# vfd.net
KiCad netlist of a schematic drawn in EAGLE
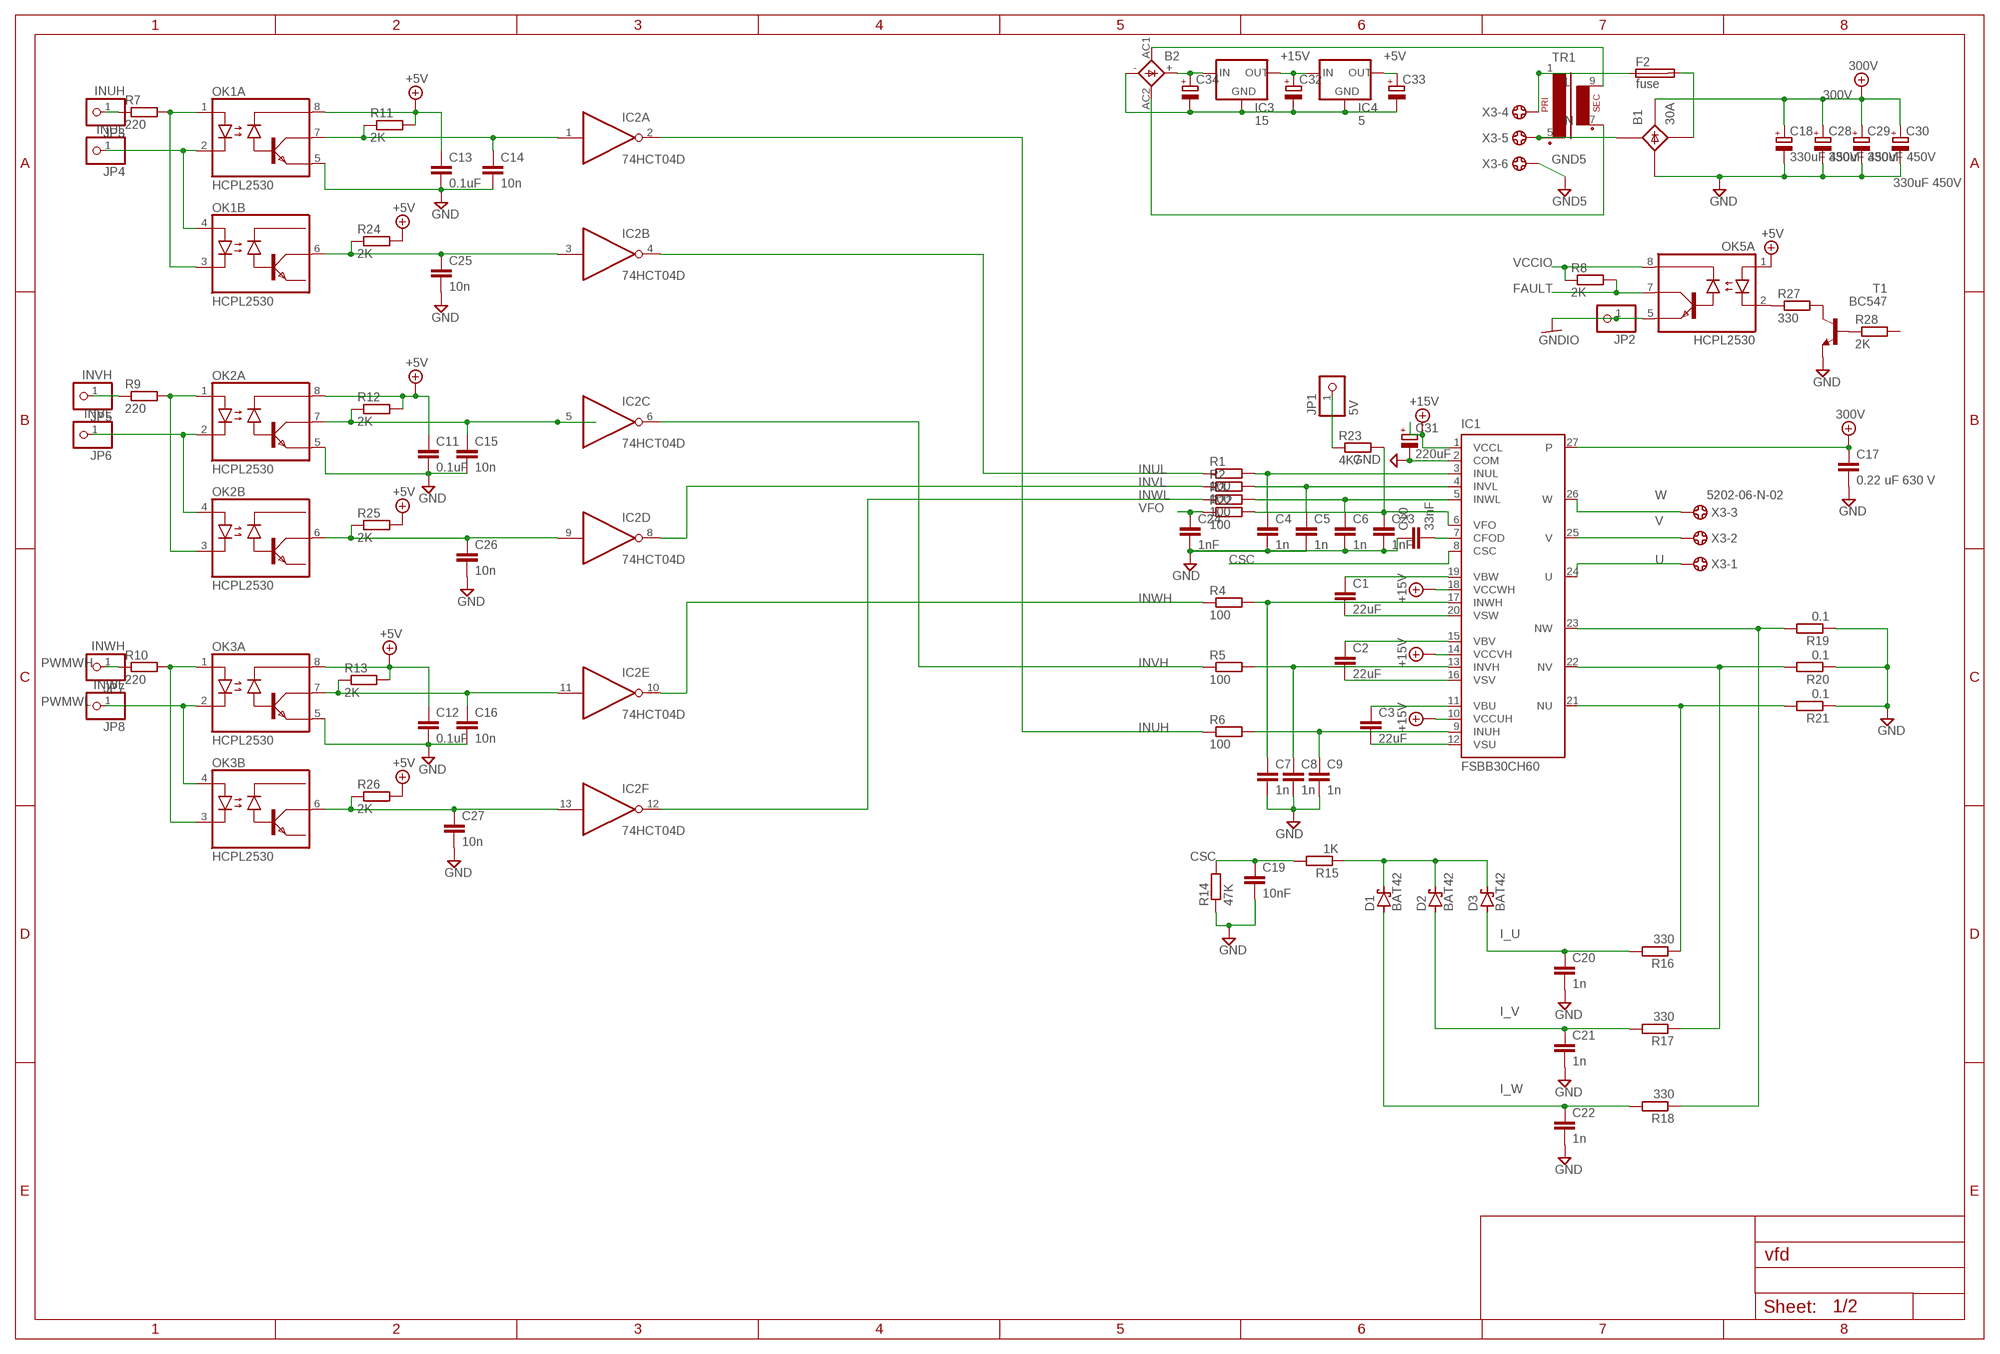
[diagram p0: schematic, sheet 1]

(export (version "E")
  (design (tool "Eeschema 10.0.6"))
  (components
    (comp (ref "B1")
      (value "30A")
      (footprint "eagle-import:B25A-")
      (libsource (lib "eagle-import") (part "B25A-"))
    )
    (comp (ref "B2")
      (value "S41")
      (footprint "eagle-import:S41")
      (libsource (lib "eagle-import") (part "S41"))
    )
    (comp (ref "C1")
      (value "22uF")
      (footprint "eagle-import:C025-024X044")
      (libsource (lib "eagle-import") (part "C-EU025-024X044"))
    )
    (comp (ref "C2")
      (value "22uF")
      (footprint "eagle-import:C025-024X044")
      (libsource (lib "eagle-import") (part "C-EU025-024X044"))
    )
    (comp (ref "C3")
      (value "22uF")
      (footprint "eagle-import:C025-024X044")
      (libsource (lib "eagle-import") (part "C-EU025-024X044"))
    )
    (comp (ref "C4")
      (value "1n")
      (footprint "eagle-import:C025-024X044")
      (libsource (lib "eagle-import") (part "C-EU025-024X044"))
    )
    (comp (ref "C5")
      (value "1n")
      (footprint "eagle-import:C025-024X044")
      (libsource (lib "eagle-import") (part "C-EU025-024X044"))
    )
    (comp (ref "C6")
      (value "1n")
      (footprint "eagle-import:C025-024X044")
      (libsource (lib "eagle-import") (part "C-EU025-024X044"))
    )
    (comp (ref "C7")
      (value "1n")
      (footprint "eagle-import:C025-024X044")
      (libsource (lib "eagle-import") (part "C-EU025-024X044"))
    )
    (comp (ref "C8")
      (value "1n")
      (footprint "eagle-import:C025-024X044")
      (libsource (lib "eagle-import") (part "C-EU025-024X044"))
    )
    (comp (ref "C9")
      (value "1n")
      (footprint "eagle-import:C025-024X044")
      (libsource (lib "eagle-import") (part "C-EU025-024X044"))
    )
    (comp (ref "C10")
      (value "33nF")
      (footprint "eagle-import:C025-024X044")
      (libsource (lib "eagle-import") (part "C-EU025-024X044"))
    )
    (comp (ref "C11")
      (value "0.1uF")
      (footprint "eagle-import:C050-025X075")
      (libsource (lib "eagle-import") (part "C-EU050-025X075"))
    )
    (comp (ref "C12")
      (value "0.1uF")
      (footprint "eagle-import:C050-025X075")
      (libsource (lib "eagle-import") (part "C-EU050-025X075"))
    )
    (comp (ref "C13")
      (value "0.1uF")
      (footprint "eagle-import:C050-025X075")
      (libsource (lib "eagle-import") (part "C-EU050-025X075"))
    )
    (comp (ref "C14")
      (value "10n")
      (footprint "eagle-import:C025-024X044")
      (libsource (lib "eagle-import") (part "C-EU025-024X044"))
    )
    (comp (ref "C15")
      (value "10n")
      (footprint "eagle-import:C025-024X044")
      (libsource (lib "eagle-import") (part "C-EU025-024X044"))
    )
    (comp (ref "C16")
      (value "10n")
      (footprint "eagle-import:C025-024X044")
      (libsource (lib "eagle-import") (part "C-EU025-024X044"))
    )
    (comp (ref "C17")
      (value "0.22 uF 630 V")
      (footprint "eagle-import:C150-091X182")
      (libsource (lib "eagle-import") (part "C-EU150-091X182"))
    )
    (comp (ref "C18")
      (value "330uF 450V")
      (footprint "eagle-import:EB35D")
      (libsource (lib "eagle-import") (part "CPOL-EUE10-35"))
    )
    (comp (ref "C19")
      (value "10nF")
      (footprint "eagle-import:C025-024X044")
      (libsource (lib "eagle-import") (part "C-EU025-024X044"))
    )
    (comp (ref "C20")
      (value "1n")
      (footprint "eagle-import:C025-024X044")
      (libsource (lib "eagle-import") (part "C-EU025-024X044"))
    )
    (comp (ref "C21")
      (value "1n")
      (footprint "eagle-import:C025-024X044")
      (libsource (lib "eagle-import") (part "C-EU025-024X044"))
    )
    (comp (ref "C22")
      (value "1n")
      (footprint "eagle-import:C025-024X044")
      (libsource (lib "eagle-import") (part "C-EU025-024X044"))
    )
    (comp (ref "C23")
      (value "1nF")
      (footprint "eagle-import:C025-024X044")
      (libsource (lib "eagle-import") (part "C-EU025-024X044"))
    )
    (comp (ref "C24")
      (value "1nF")
      (footprint "eagle-import:C025-024X044")
      (libsource (lib "eagle-import") (part "C-EU025-024X044"))
    )
    (comp (ref "C25")
      (value "10n")
      (footprint "eagle-import:C025-024X044")
      (libsource (lib "eagle-import") (part "C-EU025-024X044"))
    )
    (comp (ref "C26")
      (value "10n")
      (footprint "eagle-import:C025-024X044")
      (libsource (lib "eagle-import") (part "C-EU025-024X044"))
    )
    (comp (ref "C27")
      (value "10n")
      (footprint "eagle-import:C025-024X044")
      (libsource (lib "eagle-import") (part "C-EU025-024X044"))
    )
    (comp (ref "C28")
      (value "330uF 450V")
      (footprint "eagle-import:EB35D")
      (libsource (lib "eagle-import") (part "CPOL-EUE10-35"))
    )
    (comp (ref "C29")
      (value "330uF 450V")
      (footprint "eagle-import:EB35D")
      (libsource (lib "eagle-import") (part "CPOL-EUE10-35"))
    )
    (comp (ref "C30")
      (value "330uF 450V")
      (footprint "eagle-import:EB35D")
      (libsource (lib "eagle-import") (part "CPOL-EUE10-35"))
    )
    (comp (ref "C31")
      (value "220uF")
      (footprint "eagle-import:B45181B")
      (libsource (lib "eagle-import") (part "CPOL-EUB45181B"))
    )
    (comp (ref "C32")
      (value "CPOL-EUB45181A")
      (footprint "eagle-import:B45181A")
      (libsource (lib "eagle-import") (part "CPOL-EUB45181A"))
    )
    (comp (ref "C33")
      (value "CPOL-EUB45181A")
      (footprint "eagle-import:B45181A")
      (libsource (lib "eagle-import") (part "CPOL-EUB45181A"))
    )
    (comp (ref "C34")
      (value "CPOL-EUB45181A")
      (footprint "eagle-import:B45181A")
      (libsource (lib "eagle-import") (part "CPOL-EUB45181A"))
    )
    (comp (ref "D1")
      (value "BAT42")
      (footprint "eagle-import:DO35-10")
      (libsource (lib "eagle-import") (part "BAT42"))
    )
    (comp (ref "D2")
      (value "BAT42")
      (footprint "eagle-import:DO35-10")
      (libsource (lib "eagle-import") (part "BAT42"))
    )
    (comp (ref "D3")
      (value "BAT42")
      (footprint "eagle-import:DO35-10")
      (libsource (lib "eagle-import") (part "BAT42"))
    )
    (comp (ref "F2")
      (value "fuse")
      (footprint "eagle-import:SH22")
      (libsource (lib "eagle-import") (part "SH22"))
    )
    (comp (ref "IC1")
      (value "FSBB30CH60")
      (footprint "eagle-import:FSBB30CH60")
      (fields (field (name "MF") "ON Semiconductor"))
      (libsource (lib "eagle-import") (part "FSBB30CH60"))
    )
    (comp (ref "IC2")
      (value "74HCT04D")
      (footprint "eagle-import:SO14")
      (libsource (lib "eagle-import") (part "7404DHCT"))
    )
    (comp (ref "IC3")
      (value "15")
      (footprint "eagle-import:78MXXL")
      (libsource (lib "eagle-import") (part "78MXXL"))
    )
    (comp (ref "IC4")
      (value "5")
      (footprint "eagle-import:78MXXL")
      (libsource (lib "eagle-import") (part "78MXXL"))
    )
    (comp (ref "JP1")
      (value "5V")
      (footprint "eagle-import:1X01")
      (libsource (lib "eagle-import") (part "PINHD-1X1"))
    )
    (comp (ref "JP2")
      (value "PINHD-1X1")
      (footprint "eagle-import:1X01")
      (libsource (lib "eagle-import") (part "PINHD-1X1"))
    )
    (comp (ref "JP3")
      (value "INUH")
      (footprint "eagle-import:1X01")
      (libsource (lib "eagle-import") (part "PINHD-1X1"))
    )
    (comp (ref "JP4")
      (value "INUL")
      (footprint "eagle-import:1X01")
      (libsource (lib "eagle-import") (part "PINHD-1X1"))
    )
    (comp (ref "JP5")
      (value "INVH")
      (footprint "eagle-import:1X01")
      (libsource (lib "eagle-import") (part "PINHD-1X1"))
    )
    (comp (ref "JP6")
      (value "INVL")
      (footprint "eagle-import:1X01")
      (libsource (lib "eagle-import") (part "PINHD-1X1"))
    )
    (comp (ref "JP7")
      (value "INWH")
      (footprint "eagle-import:1X01")
      (libsource (lib "eagle-import") (part "PINHD-1X1"))
    )
    (comp (ref "JP8")
      (value "INWL")
      (footprint "eagle-import:1X01")
      (libsource (lib "eagle-import") (part "PINHD-1X1"))
    )
    (comp (ref "OK1")
      (value "HCPL2530")
      (footprint "eagle-import:DIL08")
      (fields (field (name "MF") "AGILENT TECHNOLOGIES") (field (name "MPN") "HCPL-2530-000E"))
      (libsource (lib "eagle-import") (part "HCPL2530"))
    )
    (comp (ref "OK2")
      (value "HCPL2530")
      (footprint "eagle-import:DIL08")
      (fields (field (name "MF") "AGILENT TECHNOLOGIES") (field (name "MPN") "HCPL-2530-000E"))
      (libsource (lib "eagle-import") (part "HCPL2530"))
    )
    (comp (ref "OK3")
      (value "HCPL2530")
      (footprint "eagle-import:DIL08")
      (fields (field (name "MF") "AGILENT TECHNOLOGIES") (field (name "MPN") "HCPL-2530-000E"))
      (libsource (lib "eagle-import") (part "HCPL2530"))
    )
    (comp (ref "OK5")
      (value "HCPL2530")
      (footprint "eagle-import:DIL08")
      (fields (field (name "MF") "AGILENT TECHNOLOGIES") (field (name "MPN") "HCPL-2530-000E"))
      (libsource (lib "eagle-import") (part "HCPL2530"))
    )
    (comp (ref "R1")
      (value "100")
      (footprint "eagle-import:0204_7")
      (libsource (lib "eagle-import") (part "R-EU_0204/7"))
    )
    (comp (ref "R2")
      (value "100")
      (footprint "eagle-import:0204_7")
      (libsource (lib "eagle-import") (part "R-EU_0204/7"))
    )
    (comp (ref "R3")
      (value "100")
      (footprint "eagle-import:0204_7")
      (libsource (lib "eagle-import") (part "R-EU_0204/7"))
    )
    (comp (ref "R4")
      (value "100")
      (footprint "eagle-import:0204_7")
      (libsource (lib "eagle-import") (part "R-EU_0204/7"))
    )
    (comp (ref "R5")
      (value "100")
      (footprint "eagle-import:0204_7")
      (libsource (lib "eagle-import") (part "R-EU_0204/7"))
    )
    (comp (ref "R6")
      (value "100")
      (footprint "eagle-import:0204_7")
      (libsource (lib "eagle-import") (part "R-EU_0204/7"))
    )
    (comp (ref "R7")
      (value "220")
      (footprint "eagle-import:0204_7")
      (libsource (lib "eagle-import") (part "R-EU_0204/7"))
    )
    (comp (ref "R8")
      (value "2K")
      (footprint "eagle-import:0204_7")
      (libsource (lib "eagle-import") (part "R-EU_0204/7"))
    )
    (comp (ref "R9")
      (value "220")
      (footprint "eagle-import:0204_7")
      (libsource (lib "eagle-import") (part "R-EU_0204/7"))
    )
    (comp (ref "R10")
      (value "220")
      (footprint "eagle-import:0204_7")
      (libsource (lib "eagle-import") (part "R-EU_0204/7"))
    )
    (comp (ref "R11")
      (value "2K")
      (footprint "eagle-import:0204_7")
      (libsource (lib "eagle-import") (part "R-EU_0204/7"))
    )
    (comp (ref "R12")
      (value "2K")
      (footprint "eagle-import:0204_7")
      (libsource (lib "eagle-import") (part "R-EU_0204/7"))
    )
    (comp (ref "R13")
      (value "2K")
      (footprint "eagle-import:0204_7")
      (libsource (lib "eagle-import") (part "R-EU_0204/7"))
    )
    (comp (ref "R14")
      (value "47K")
      (footprint "eagle-import:0204_7")
      (libsource (lib "eagle-import") (part "R-EU_0204/7"))
    )
    (comp (ref "R15")
      (value "1K")
      (footprint "eagle-import:0204_7")
      (libsource (lib "eagle-import") (part "R-EU_0204/7"))
    )
    (comp (ref "R16")
      (value "330")
      (footprint "eagle-import:0204_7")
      (libsource (lib "eagle-import") (part "R-EU_0204/7"))
    )
    (comp (ref "R17")
      (value "330")
      (footprint "eagle-import:0204_7")
      (libsource (lib "eagle-import") (part "R-EU_0204/7"))
    )
    (comp (ref "R18")
      (value "330")
      (footprint "eagle-import:0204_7")
      (libsource (lib "eagle-import") (part "R-EU_0204/7"))
    )
    (comp (ref "R19")
      (value "0.1")
      (footprint "eagle-import:0204_7")
      (libsource (lib "eagle-import") (part "R-EU_0204/7"))
    )
    (comp (ref "R20")
      (value "0.1")
      (footprint "eagle-import:0204_7")
      (libsource (lib "eagle-import") (part "R-EU_0204/7"))
    )
    (comp (ref "R21")
      (value "0.1")
      (footprint "eagle-import:0204_7")
      (libsource (lib "eagle-import") (part "R-EU_0204/7"))
    )
    (comp (ref "R22")
      (value "100")
      (footprint "eagle-import:0204_7")
      (libsource (lib "eagle-import") (part "R-EU_0204/7"))
    )
    (comp (ref "R23")
      (value "4K7")
      (footprint "eagle-import:0204_7")
      (libsource (lib "eagle-import") (part "R-EU_0204/7"))
    )
    (comp (ref "R24")
      (value "2K")
      (footprint "eagle-import:0204_7")
      (libsource (lib "eagle-import") (part "R-EU_0204/7"))
    )
    (comp (ref "R25")
      (value "2K")
      (footprint "eagle-import:0204_7")
      (libsource (lib "eagle-import") (part "R-EU_0204/7"))
    )
    (comp (ref "R26")
      (value "2K")
      (footprint "eagle-import:0204_7")
      (libsource (lib "eagle-import") (part "R-EU_0204/7"))
    )
    (comp (ref "R27")
      (value "330")
      (footprint "eagle-import:0204_7")
      (libsource (lib "eagle-import") (part "R-EU_0204/7"))
    )
    (comp (ref "R28")
      (value "2K")
      (footprint "eagle-import:0204_7")
      (libsource (lib "eagle-import") (part "R-EU_0204/7"))
    )
    (comp (ref "T1")
      (value "BC547")
      (footprint "eagle-import:TO92")
      (libsource (lib "eagle-import") (part "BC547"))
    )
    (comp (ref "TR1")
      (value "EI30-1")
      (footprint "eagle-import:EI30-1")
      (libsource (lib "eagle-import") (part "EI30-1"))
    )
    (comp (ref "X3")
      (value "5202-06-N-02")
      (footprint "eagle-import:5202-06-N-02")
      (libsource (lib "eagle-import") (part "5202-06-N-02"))
    )
  )
  (nets
    (net (code "1") (name "+5V") (class "Default")
      (node (ref "C11") (pin "1") (pinfunction "1_1") (pintype "passive"))
      (node (ref "C12") (pin "1") (pinfunction "1_1") (pintype "passive"))
      (node (ref "C13") (pin "1") (pinfunction "1_1") (pintype "passive"))
      (node (ref "C33") (pin "+") (pinfunction "+_+") (pintype "passive"))
      (node (ref "IC4") (pin "OUT") (pinfunction "OUT_OUT") (pintype "passive"))
      (node (ref "OK1") (pin "8") (pinfunction "VCC_8") (pintype "passive"))
      (node (ref "OK2") (pin "8") (pinfunction "VCC_8") (pintype "passive"))
      (node (ref "OK3") (pin "8") (pinfunction "VCC_8") (pintype "passive"))
      (node (ref "OK5") (pin "1") (pinfunction "A1_1") (pintype "passive"))
      (node (ref "R11") (pin "2") (pinfunction "2_2") (pintype "passive"))
      (node (ref "R12") (pin "2") (pinfunction "2_2") (pintype "passive"))
      (node (ref "R13") (pin "2") (pinfunction "2_2") (pintype "passive"))
      (node (ref "R24") (pin "2") (pinfunction "2_2") (pintype "passive"))
      (node (ref "R25") (pin "2") (pinfunction "2_2") (pintype "passive"))
      (node (ref "R26") (pin "2") (pinfunction "2_2") (pintype "passive"))
    )
    (net (code "2") (name "+15V") (class "Default")
      (node (ref "C31") (pin "+") (pinfunction "+_+") (pintype "passive"))
      (node (ref "C32") (pin "+") (pinfunction "+_+") (pintype "passive"))
      (node (ref "IC1") (pin "1") (pinfunction "VCCL_1") (pintype "power_in"))
      (node (ref "IC1") (pin "10") (pinfunction "VCCUH_10") (pintype "input"))
      (node (ref "IC1") (pin "14") (pinfunction "VCCVH_14") (pintype "input"))
      (node (ref "IC1") (pin "18") (pinfunction "VCCWH_18") (pintype "input"))
      (node (ref "IC3") (pin "OUT") (pinfunction "OUT_OUT") (pintype "passive"))
      (node (ref "IC4") (pin "IN") (pinfunction "IN_IN") (pintype "input"))
    )
    (net (code "3") (name "300V") (class "Default")
      (node (ref "B1") (pin "+1") (pinfunction "+_+1") (pintype "passive"))
      (node (ref "C17") (pin "1") (pinfunction "1_1") (pintype "passive"))
      (node (ref "C18") (pin "+") (pinfunction "+_+") (pintype "passive"))
      (node (ref "C28") (pin "+") (pinfunction "+_+") (pintype "passive"))
      (node (ref "C29") (pin "+") (pinfunction "+_+") (pintype "passive"))
      (node (ref "C30") (pin "+") (pinfunction "+_+") (pintype "passive"))
      (node (ref "IC1") (pin "27") (pinfunction "P_27") (pintype "input"))
    )
    (net (code "4") (name "CSC") (class "Default")
      (node (ref "C19") (pin "1") (pinfunction "1_1") (pintype "passive"))
      (node (ref "IC1") (pin "8") (pinfunction "CSC_8") (pintype "passive"))
      (node (ref "R14") (pin "2") (pinfunction "2_2") (pintype "passive"))
      (node (ref "R15") (pin "2") (pinfunction "2_2") (pintype "passive"))
    )
    (net (code "5") (name "FAULT") (class "Default")
      (node (ref "OK5") (pin "7") (pinfunction "VO1_7") (pintype "passive"))
      (node (ref "R8") (pin "2") (pinfunction "2_2") (pintype "passive"))
    )
    (net (code "6") (name "GND") (class "Default")
      (node (ref "B1") (pin "-1") (pinfunction "-_-1") (pintype "passive"))
      (node (ref "C10") (pin "1") (pinfunction "1_1") (pintype "passive"))
      (node (ref "C11") (pin "2") (pinfunction "2_2") (pintype "passive"))
      (node (ref "C12") (pin "2") (pinfunction "2_2") (pintype "passive"))
      (node (ref "C13") (pin "2") (pinfunction "2_2") (pintype "passive"))
      (node (ref "C14") (pin "2") (pinfunction "2_2") (pintype "passive"))
      (node (ref "C15") (pin "2") (pinfunction "2_2") (pintype "passive"))
      (node (ref "C16") (pin "2") (pinfunction "2_2") (pintype "passive"))
      (node (ref "C17") (pin "2") (pinfunction "2_2") (pintype "passive"))
      (node (ref "C18") (pin "-") (pinfunction "-_-") (pintype "passive"))
      (node (ref "C19") (pin "2") (pinfunction "2_2") (pintype "passive"))
      (node (ref "C20") (pin "2") (pinfunction "2_2") (pintype "passive"))
      (node (ref "C21") (pin "2") (pinfunction "2_2") (pintype "passive"))
      (node (ref "C22") (pin "2") (pinfunction "2_2") (pintype "passive"))
      (node (ref "C23") (pin "2") (pinfunction "2_2") (pintype "passive"))
      (node (ref "C24") (pin "2") (pinfunction "2_2") (pintype "passive"))
      (node (ref "C25") (pin "2") (pinfunction "2_2") (pintype "passive"))
      (node (ref "C26") (pin "2") (pinfunction "2_2") (pintype "passive"))
      (node (ref "C27") (pin "2") (pinfunction "2_2") (pintype "passive"))
      (node (ref "C28") (pin "-") (pinfunction "-_-") (pintype "passive"))
      (node (ref "C29") (pin "-") (pinfunction "-_-") (pintype "passive"))
      (node (ref "C30") (pin "-") (pinfunction "-_-") (pintype "passive"))
      (node (ref "C31") (pin "-") (pinfunction "-_-") (pintype "passive"))
      (node (ref "C4") (pin "2") (pinfunction "2_2") (pintype "passive"))
      (node (ref "C5") (pin "2") (pinfunction "2_2") (pintype "passive"))
      (node (ref "C6") (pin "2") (pinfunction "2_2") (pintype "passive"))
      (node (ref "C7") (pin "2") (pinfunction "2_2") (pintype "passive"))
      (node (ref "C8") (pin "2") (pinfunction "2_2") (pintype "passive"))
      (node (ref "C9") (pin "2") (pinfunction "2_2") (pintype "passive"))
      (node (ref "IC1") (pin "2") (pinfunction "COM_2") (pintype "power_in"))
      (node (ref "OK1") (pin "5") (pinfunction "GND_5") (pintype "passive"))
      (node (ref "OK2") (pin "5") (pinfunction "GND_5") (pintype "passive"))
      (node (ref "OK3") (pin "5") (pinfunction "GND_5") (pintype "passive"))
      (node (ref "R14") (pin "1") (pinfunction "1_1") (pintype "passive"))
      (node (ref "R19") (pin "1") (pinfunction "1_1") (pintype "passive"))
      (node (ref "R20") (pin "1") (pinfunction "1_1") (pintype "passive"))
      (node (ref "R21") (pin "1") (pinfunction "1_1") (pintype "passive"))
      (node (ref "T1") (pin "1") (pinfunction "E_1") (pintype "passive"))
    )
    (net (code "7") (name "GND5") (class "Default")
      (node (ref "X3") (pin "6") (pinfunction "1_6") (pintype "passive"))
    )
    (net (code "8") (name "GNDIO") (class "Default")
      (node (ref "JP2") (pin "1") (pinfunction "1_1") (pintype "passive"))
      (node (ref "OK5") (pin "5") (pinfunction "GND_5") (pintype "passive"))
    )
    (net (code "9") (name "INUH") (class "Default")
      (node (ref "IC2") (pin "2") (pinfunction "O_2") (pintype "output"))
      (node (ref "R6") (pin "1") (pinfunction "1_1") (pintype "passive"))
    )
    (net (code "10") (name "INUL") (class "Default")
      (node (ref "IC2") (pin "4") (pinfunction "O_4") (pintype "output"))
      (node (ref "R1") (pin "1") (pinfunction "1_1") (pintype "passive"))
    )
    (net (code "11") (name "INVH") (class "Default")
      (node (ref "IC2") (pin "6") (pinfunction "O_6") (pintype "output"))
      (node (ref "R5") (pin "1") (pinfunction "1_1") (pintype "passive"))
    )
    (net (code "12") (name "INVL") (class "Default")
      (node (ref "IC2") (pin "8") (pinfunction "O_8") (pintype "output"))
      (node (ref "R2") (pin "1") (pinfunction "1_1") (pintype "passive"))
    )
    (net (code "13") (name "INWH") (class "Default")
      (node (ref "IC2") (pin "10") (pinfunction "O_10") (pintype "output"))
      (node (ref "R4") (pin "1") (pinfunction "1_1") (pintype "passive"))
    )
    (net (code "14") (name "INWL") (class "Default")
      (node (ref "IC2") (pin "12") (pinfunction "O_12") (pintype "output"))
      (node (ref "R3") (pin "1") (pinfunction "1_1") (pintype "passive"))
    )
    (net (code "15") (name "I_U") (class "Default")
      (node (ref "C20") (pin "1") (pinfunction "1_1") (pintype "passive"))
      (node (ref "D3") (pin "A") (pinfunction "A_A") (pintype "passive"))
      (node (ref "R16") (pin "2") (pinfunction "2_2") (pintype "passive"))
    )
    (net (code "16") (name "I_V") (class "Default")
      (node (ref "C21") (pin "1") (pinfunction "1_1") (pintype "passive"))
      (node (ref "D2") (pin "A") (pinfunction "A_A") (pintype "passive"))
      (node (ref "R17") (pin "2") (pinfunction "2_2") (pintype "passive"))
    )
    (net (code "17") (name "I_W") (class "Default")
      (node (ref "C22") (pin "1") (pinfunction "1_1") (pintype "passive"))
      (node (ref "D1") (pin "A") (pinfunction "A_A") (pintype "passive"))
      (node (ref "R18") (pin "2") (pinfunction "2_2") (pintype "passive"))
    )
    (net (code "18") (name "L") (class "Default")
      (node (ref "F2") (pin "1") (pinfunction "1_1") (pintype "passive"))
      (node (ref "TR1") (pin "1") (pinfunction "P1_1") (pintype "passive"))
      (node (ref "X3") (pin "4") (pinfunction "1_4") (pintype "passive"))
    )
    (net (code "19") (name "N") (class "Default")
      (node (ref "B1") (pin "AC1-") (pinfunction "AC1_AC1-") (pintype "passive"))
      (node (ref "TR1") (pin "5") (pinfunction "P2_5") (pintype "passive"))
      (node (ref "X3") (pin "5") (pinfunction "1_5") (pintype "passive"))
    )
    (net (code "20") (name "Net-(B1-AC2-PadAC2-)") (class "Default")
      (node (ref "B1") (pin "AC2-") (pinfunction "AC2_AC2-") (pintype "passive"))
      (node (ref "F2") (pin "2") (pinfunction "2_2") (pintype "passive"))
    )
    (net (code "21") (name "Net-(B2-Pad+)") (class "Default")
      (node (ref "B2") (pin "+") (pinfunction "+_+") (pintype "passive"))
      (node (ref "C34") (pin "+") (pinfunction "+_+") (pintype "passive"))
      (node (ref "IC3") (pin "IN") (pinfunction "IN_IN") (pintype "input"))
    )
    (net (code "22") (name "Net-(B2-Pad-)") (class "Default")
      (node (ref "B2") (pin "-") (pinfunction "-_-") (pintype "passive"))
      (node (ref "C32") (pin "-") (pinfunction "-_-") (pintype "passive"))
      (node (ref "C33") (pin "-") (pinfunction "-_-") (pintype "passive"))
      (node (ref "C34") (pin "-") (pinfunction "-_-") (pintype "passive"))
      (node (ref "IC3") (pin "GND") (pinfunction "GND_GND") (pintype "input"))
      (node (ref "IC4") (pin "GND") (pinfunction "GND_GND") (pintype "input"))
    )
    (net (code "23") (name "Net-(D1-PadC)") (class "Default")
      (node (ref "D1") (pin "C") (pinfunction "C_C") (pintype "passive"))
      (node (ref "D2") (pin "C") (pinfunction "C_C") (pintype "passive"))
      (node (ref "D3") (pin "C") (pinfunction "C_C") (pintype "passive"))
      (node (ref "R15") (pin "1") (pinfunction "1_1") (pintype "passive"))
    )
    (net (code "24") (name "Net-(IC1-CFOD)") (class "Default")
      (node (ref "C10") (pin "2") (pinfunction "2_2") (pintype "passive"))
      (node (ref "IC1") (pin "7") (pinfunction "CFOD_7") (pintype "passive"))
    )
    (net (code "25") (name "Net-(IC1-INUH)") (class "Default")
      (node (ref "C9") (pin "1") (pinfunction "1_1") (pintype "passive"))
      (node (ref "IC1") (pin "9") (pinfunction "INUH_9") (pintype "input"))
      (node (ref "R6") (pin "2") (pinfunction "2_2") (pintype "passive"))
    )
    (net (code "26") (name "Net-(IC1-INUL)") (class "Default")
      (node (ref "C4") (pin "1") (pinfunction "1_1") (pintype "passive"))
      (node (ref "IC1") (pin "3") (pinfunction "INUL_3") (pintype "input"))
      (node (ref "R1") (pin "2") (pinfunction "2_2") (pintype "passive"))
    )
    (net (code "27") (name "Net-(IC1-INVH)") (class "Default")
      (node (ref "C8") (pin "1") (pinfunction "1_1") (pintype "passive"))
      (node (ref "IC1") (pin "13") (pinfunction "INVH_13") (pintype "input"))
      (node (ref "R5") (pin "2") (pinfunction "2_2") (pintype "passive"))
    )
    (net (code "28") (name "Net-(IC1-INVL)") (class "Default")
      (node (ref "C5") (pin "1") (pinfunction "1_1") (pintype "passive"))
      (node (ref "IC1") (pin "4") (pinfunction "INVL_4") (pintype "input"))
      (node (ref "R2") (pin "2") (pinfunction "2_2") (pintype "passive"))
    )
    (net (code "29") (name "Net-(IC1-INWH)") (class "Default")
      (node (ref "C7") (pin "1") (pinfunction "1_1") (pintype "passive"))
      (node (ref "IC1") (pin "17") (pinfunction "INWH_17") (pintype "input"))
      (node (ref "R4") (pin "2") (pinfunction "2_2") (pintype "passive"))
    )
    (net (code "30") (name "Net-(IC1-INWL)") (class "Default")
      (node (ref "C6") (pin "1") (pinfunction "1_1") (pintype "passive"))
      (node (ref "IC1") (pin "5") (pinfunction "INWL_5") (pintype "input"))
      (node (ref "R3") (pin "2") (pinfunction "2_2") (pintype "passive"))
    )
    (net (code "31") (name "Net-(IC1-NU)") (class "Default")
      (node (ref "IC1") (pin "21") (pinfunction "NU_21") (pintype "input"))
      (node (ref "R16") (pin "1") (pinfunction "1_1") (pintype "passive"))
      (node (ref "R21") (pin "2") (pinfunction "2_2") (pintype "passive"))
    )
    (net (code "32") (name "Net-(IC1-NV)") (class "Default")
      (node (ref "IC1") (pin "22") (pinfunction "NV_22") (pintype "input"))
      (node (ref "R17") (pin "1") (pinfunction "1_1") (pintype "passive"))
      (node (ref "R20") (pin "2") (pinfunction "2_2") (pintype "passive"))
    )
    (net (code "33") (name "Net-(IC1-NW)") (class "Default")
      (node (ref "IC1") (pin "23") (pinfunction "NW_23") (pintype "input"))
      (node (ref "R18") (pin "1") (pinfunction "1_1") (pintype "passive"))
      (node (ref "R19") (pin "2") (pinfunction "2_2") (pintype "passive"))
    )
    (net (code "34") (name "Net-(IC1-VBU)") (class "Default")
      (node (ref "C3") (pin "1") (pinfunction "1_1") (pintype "passive"))
      (node (ref "IC1") (pin "11") (pinfunction "VBU_11") (pintype "input"))
    )
    (net (code "35") (name "Net-(IC1-VBV)") (class "Default")
      (node (ref "C2") (pin "1") (pinfunction "1_1") (pintype "passive"))
      (node (ref "IC1") (pin "15") (pinfunction "VBV_15") (pintype "input"))
    )
    (net (code "36") (name "Net-(IC1-VBW)") (class "Default")
      (node (ref "C1") (pin "1") (pinfunction "1_1") (pintype "passive"))
      (node (ref "IC1") (pin "19") (pinfunction "VBW_19") (pintype "input"))
    )
    (net (code "37") (name "Net-(IC1-VFO)") (class "Default")
      (node (ref "C23") (pin "1") (pinfunction "1_1") (pintype "passive"))
      (node (ref "IC1") (pin "6") (pinfunction "VFO_6") (pintype "output"))
      (node (ref "R22") (pin "2") (pinfunction "2_2") (pintype "passive"))
      (node (ref "R23") (pin "2") (pinfunction "2_2") (pintype "passive"))
    )
    (net (code "38") (name "Net-(IC1-VSU)") (class "Default")
      (node (ref "C3") (pin "2") (pinfunction "2_2") (pintype "passive"))
      (node (ref "IC1") (pin "12") (pinfunction "VSU_12") (pintype "input"))
    )
    (net (code "39") (name "Net-(IC1-VSV)") (class "Default")
      (node (ref "C2") (pin "2") (pinfunction "2_2") (pintype "passive"))
      (node (ref "IC1") (pin "16") (pinfunction "VSV_16") (pintype "input"))
    )
    (net (code "40") (name "Net-(IC1-VSW)") (class "Default")
      (node (ref "C1") (pin "2") (pinfunction "2_2") (pintype "passive"))
      (node (ref "IC1") (pin "20") (pinfunction "VSW_20") (pintype "input"))
    )
    (net (code "41") (name "Net-(IC2A-I)") (class "Default")
      (node (ref "C14") (pin "1") (pinfunction "1_1") (pintype "passive"))
      (node (ref "IC2") (pin "1") (pinfunction "I_1") (pintype "input"))
      (node (ref "OK1") (pin "7") (pinfunction "VO1_7") (pintype "passive"))
      (node (ref "R11") (pin "1") (pinfunction "1_1") (pintype "passive"))
    )
    (net (code "42") (name "Net-(IC2B-I)") (class "Default")
      (node (ref "C25") (pin "1") (pinfunction "1_1") (pintype "passive"))
      (node (ref "IC2") (pin "3") (pinfunction "I_3") (pintype "input"))
      (node (ref "OK1") (pin "6") (pinfunction "VO2_6") (pintype "passive"))
      (node (ref "R24") (pin "1") (pinfunction "1_1") (pintype "passive"))
    )
    (net (code "43") (name "Net-(IC2C-I)") (class "Default")
      (node (ref "C15") (pin "1") (pinfunction "1_1") (pintype "passive"))
      (node (ref "IC2") (pin "5") (pinfunction "I_5") (pintype "input"))
      (node (ref "OK2") (pin "7") (pinfunction "VO1_7") (pintype "passive"))
      (node (ref "R12") (pin "1") (pinfunction "1_1") (pintype "passive"))
    )
    (net (code "44") (name "Net-(IC2D-I)") (class "Default")
      (node (ref "C26") (pin "1") (pinfunction "1_1") (pintype "passive"))
      (node (ref "IC2") (pin "9") (pinfunction "I_9") (pintype "input"))
      (node (ref "OK2") (pin "6") (pinfunction "VO2_6") (pintype "passive"))
      (node (ref "R25") (pin "1") (pinfunction "1_1") (pintype "passive"))
    )
    (net (code "45") (name "Net-(IC2E-I)") (class "Default")
      (node (ref "C16") (pin "1") (pinfunction "1_1") (pintype "passive"))
      (node (ref "IC2") (pin "11") (pinfunction "I_11") (pintype "input"))
      (node (ref "OK3") (pin "7") (pinfunction "VO1_7") (pintype "passive"))
      (node (ref "R13") (pin "1") (pinfunction "1_1") (pintype "passive"))
    )
    (net (code "46") (name "Net-(IC2F-I)") (class "Default")
      (node (ref "C27") (pin "1") (pinfunction "1_1") (pintype "passive"))
      (node (ref "IC2") (pin "13") (pinfunction "I_13") (pintype "input"))
      (node (ref "OK3") (pin "6") (pinfunction "VO2_6") (pintype "passive"))
      (node (ref "R26") (pin "1") (pinfunction "1_1") (pintype "passive"))
    )
    (net (code "47") (name "Net-(JP1-Pad1)") (class "Default")
      (node (ref "JP1") (pin "1") (pinfunction "1_1") (pintype "passive"))
      (node (ref "R23") (pin "1") (pinfunction "1_1") (pintype "passive"))
    )
    (net (code "48") (name "Net-(JP3-Pad1)") (class "Default")
      (node (ref "JP3") (pin "1") (pinfunction "1_1") (pintype "passive"))
      (node (ref "R7") (pin "1") (pinfunction "1_1") (pintype "passive"))
    )
    (net (code "49") (name "Net-(JP5-Pad1)") (class "Default")
      (node (ref "JP5") (pin "1") (pinfunction "1_1") (pintype "passive"))
      (node (ref "R9") (pin "1") (pinfunction "1_1") (pintype "passive"))
    )
    (net (code "50") (name "Net-(OK1A-A1)") (class "Default")
      (node (ref "OK1") (pin "1") (pinfunction "A1_1") (pintype "passive"))
      (node (ref "OK1") (pin "3") (pinfunction "C2_3") (pintype "passive"))
      (node (ref "R7") (pin "2") (pinfunction "2_2") (pintype "passive"))
    )
    (net (code "51") (name "Net-(OK1A-C1)") (class "Default")
      (node (ref "JP4") (pin "1") (pinfunction "1_1") (pintype "passive"))
      (node (ref "OK1") (pin "2") (pinfunction "C1_2") (pintype "passive"))
      (node (ref "OK1") (pin "4") (pinfunction "A2_4") (pintype "passive"))
    )
    (net (code "52") (name "Net-(OK2A-A1)") (class "Default")
      (node (ref "OK2") (pin "1") (pinfunction "A1_1") (pintype "passive"))
      (node (ref "OK2") (pin "3") (pinfunction "C2_3") (pintype "passive"))
      (node (ref "R9") (pin "2") (pinfunction "2_2") (pintype "passive"))
    )
    (net (code "53") (name "Net-(OK2A-C1)") (class "Default")
      (node (ref "JP6") (pin "1") (pinfunction "1_1") (pintype "passive"))
      (node (ref "OK2") (pin "2") (pinfunction "C1_2") (pintype "passive"))
      (node (ref "OK2") (pin "4") (pinfunction "A2_4") (pintype "passive"))
    )
    (net (code "54") (name "Net-(OK3A-A1)") (class "Default")
      (node (ref "OK3") (pin "1") (pinfunction "A1_1") (pintype "passive"))
      (node (ref "OK3") (pin "3") (pinfunction "C2_3") (pintype "passive"))
      (node (ref "R10") (pin "2") (pinfunction "2_2") (pintype "passive"))
    )
    (net (code "55") (name "Net-(OK5A-C1)") (class "Default")
      (node (ref "OK5") (pin "2") (pinfunction "C1_2") (pintype "passive"))
      (node (ref "R27") (pin "1") (pinfunction "1_1") (pintype "passive"))
    )
    (net (code "56") (name "Net-(T1-B)") (class "Default")
      (node (ref "R28") (pin "1") (pinfunction "1_1") (pintype "passive"))
      (node (ref "T1") (pin "2") (pinfunction "B_2") (pintype "passive"))
    )
    (net (code "57") (name "Net-(T1-C)") (class "Default")
      (node (ref "R27") (pin "2") (pinfunction "2_2") (pintype "passive"))
      (node (ref "T1") (pin "3") (pinfunction "C_3") (pintype "passive"))
    )
    (net (code "58") (name "Net-(TR1-S3)") (class "Default")
      (node (ref "B2") (pin "AC2") (pinfunction "AC2_AC2") (pintype "passive"))
      (node (ref "TR1") (pin "7") (pinfunction "S3_7") (pintype "passive"))
    )
    (net (code "59") (name "Net-(TR1-S4)") (class "Default")
      (node (ref "B2") (pin "AC1") (pinfunction "AC1_AC1") (pintype "passive"))
      (node (ref "TR1") (pin "9") (pinfunction "S4_9") (pintype "passive"))
    )
    (net (code "60") (name "PWMWH") (class "Default")
      (node (ref "JP7") (pin "1") (pinfunction "1_1") (pintype "passive"))
      (node (ref "R10") (pin "1") (pinfunction "1_1") (pintype "passive"))
    )
    (net (code "61") (name "PWMWL") (class "Default")
      (node (ref "JP8") (pin "1") (pinfunction "1_1") (pintype "passive"))
      (node (ref "OK3") (pin "2") (pinfunction "C1_2") (pintype "passive"))
      (node (ref "OK3") (pin "4") (pinfunction "A2_4") (pintype "passive"))
    )
    (net (code "62") (name "U") (class "Default")
      (node (ref "IC1") (pin "24") (pinfunction "U_24") (pintype "output"))
      (node (ref "X3") (pin "1") (pinfunction "1_1") (pintype "passive"))
    )
    (net (code "63") (name "V") (class "Default")
      (node (ref "IC1") (pin "25") (pinfunction "V_25") (pintype "output"))
      (node (ref "X3") (pin "2") (pinfunction "1_2") (pintype "passive"))
    )
    (net (code "64") (name "VCCIO") (class "Default")
      (node (ref "OK5") (pin "8") (pinfunction "VCC_8") (pintype "passive"))
      (node (ref "R8") (pin "1") (pinfunction "1_1") (pintype "passive"))
    )
    (net (code "65") (name "VFO") (class "Default")
      (node (ref "C24") (pin "1") (pinfunction "1_1") (pintype "passive"))
      (node (ref "R22") (pin "1") (pinfunction "1_1") (pintype "passive"))
    )
    (net (code "66") (name "W") (class "Default")
      (node (ref "IC1") (pin "26") (pinfunction "W_26") (pintype "output"))
      (node (ref "X3") (pin "3") (pinfunction "1_3") (pintype "passive"))
    )
    (net (code "67") (name "unconnected-(B1-Pad+)") (class "Default")
      (node (ref "B1") (pin "+") (pinfunction "+_+") (pintype "passive"))
    )
    (net (code "68") (name "unconnected-(B1-Pad-)") (class "Default")
      (node (ref "B1") (pin "-") (pinfunction "-_-") (pintype "passive"))
    )
    (net (code "69") (name "unconnected-(B1-PadAC1)") (class "Default")
      (node (ref "B1") (pin "AC1") (pinfunction "AC1_AC1") (pintype "passive"))
    )
    (net (code "70") (name "unconnected-(B1-PadAC2)") (class "Default")
      (node (ref "B1") (pin "AC2") (pinfunction "AC2_AC2") (pintype "passive"))
    )
    (net (code "71") (name "unconnected-(R28-Pad2)") (class "Default")
      (node (ref "R28") (pin "2") (pinfunction "2_2") (pintype "passive"))
    )
  )
)
